# LEDs.net
KiCad netlist of a schematic drawn in Altium Designer
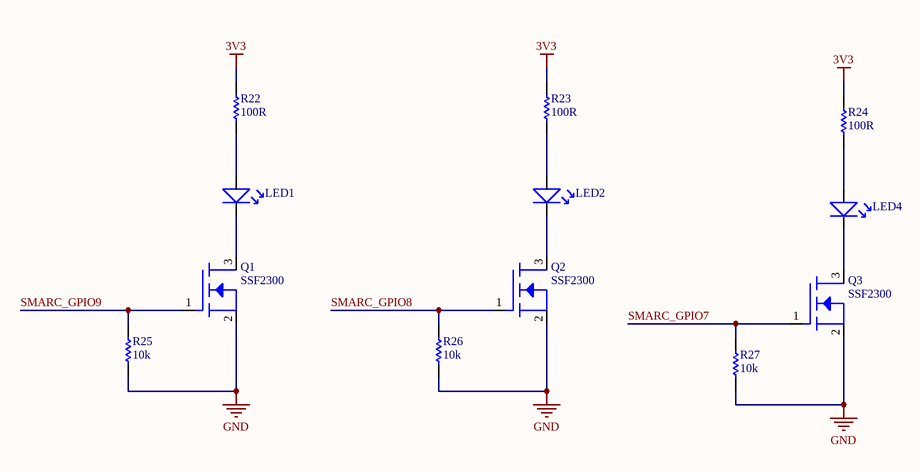
[diagram p0: LEDs.SchDoc]

(export (version "E")
  (design (tool "Eeschema 10.0.6"))
  (components
    (comp (ref "LED1") (value "0603 LED") (footprint "0603 LED") (libsource (lib "Master") (part "0603 LED")))
    (comp (ref "LED2") (value "0603 LED") (footprint "0603 LED") (libsource (lib "Master") (part "0603 LED")))
    (comp (ref "LED4") (value "0603 LED") (footprint "0603 LED") (libsource (lib "Master") (part "0603 LED")))
    (comp (ref "Q1")
      (value "SSF2300")
      (footprint "SSF2300")
      (description "NMOS 20V 4.5A SOT23")
      (libsource (lib "Master") (part "SSF2300"))
    )
    (comp (ref "Q2")
      (value "SSF2300")
      (footprint "SSF2300")
      (description "NMOS 20V 4.5A SOT23")
      (libsource (lib "Master") (part "SSF2300"))
    )
    (comp (ref "Q3")
      (value "SSF2300")
      (footprint "SSF2300")
      (description "NMOS 20V 4.5A SOT23")
      (libsource (lib "Master") (part "SSF2300"))
    )
    (comp (ref "R22")
      (value "100R")
      (footprint "RES-0603")
      (description "Resistor chip. 0603")
      (libsource (lib "Master") (part "RES-0603"))
    )
    (comp (ref "R23")
      (value "100R")
      (footprint "RES-0603")
      (description "Resistor chip. 0603")
      (libsource (lib "Master") (part "RES-0603"))
    )
    (comp (ref "R24")
      (value "100R")
      (footprint "RES-0603")
      (description "Resistor chip. 0603")
      (libsource (lib "Master") (part "RES-0603"))
    )
    (comp (ref "R25")
      (value "10k")
      (footprint "RES-0603")
      (description "Resistor chip. 0603")
      (libsource (lib "Master") (part "RES-0603"))
    )
    (comp (ref "R26")
      (value "10k")
      (footprint "RES-0603")
      (description "Resistor chip. 0603")
      (libsource (lib "Master") (part "RES-0603"))
    )
    (comp (ref "R27")
      (value "10k")
      (footprint "RES-0603")
      (description "Resistor chip. 0603")
      (libsource (lib "Master") (part "RES-0603"))
    )
  )
  (nets
    (net (code "1") (name "/SMARC_GPIO7") (class "Default")
      (node (ref "Q3") (pin "1") (pintype "passive"))
      (node (ref "R27") (pin "2") (pintype "passive"))
    )
    (net (code "2") (name "/SMARC_GPIO8") (class "Default")
      (node (ref "Q2") (pin "1") (pintype "passive"))
      (node (ref "R26") (pin "2") (pintype "passive"))
    )
    (net (code "3") (name "/SMARC_GPIO9") (class "Default")
      (node (ref "Q1") (pin "1") (pintype "passive"))
      (node (ref "R25") (pin "2") (pintype "passive"))
    )
    (net (code "4") (name "3V3") (class "Default")
      (node (ref "R22") (pin "2") (pintype "passive"))
      (node (ref "R23") (pin "2") (pintype "passive"))
      (node (ref "R24") (pin "2") (pintype "passive"))
    )
    (net (code "5") (name "GND") (class "Default")
      (node (ref "Q1") (pin "2") (pintype "passive"))
      (node (ref "Q2") (pin "2") (pintype "passive"))
      (node (ref "Q3") (pin "2") (pintype "passive"))
      (node (ref "R25") (pin "1") (pintype "passive"))
      (node (ref "R26") (pin "1") (pintype "passive"))
      (node (ref "R27") (pin "1") (pintype "passive"))
    )
    (net (code "6") (name "Net-(LED1-5)") (class "Default")
      (node (ref "LED1") (pin "2") (pinfunction "5_2") (pintype "passive"))
      (node (ref "Q1") (pin "3") (pintype "passive"))
    )
    (net (code "7") (name "Net-(LED1-6)") (class "Default")
      (node (ref "LED1") (pin "1") (pinfunction "6_1") (pintype "passive"))
      (node (ref "R22") (pin "1") (pintype "passive"))
    )
    (net (code "8") (name "Net-(LED2-5)") (class "Default")
      (node (ref "LED2") (pin "2") (pinfunction "5_2") (pintype "passive"))
      (node (ref "Q2") (pin "3") (pintype "passive"))
    )
    (net (code "9") (name "Net-(LED2-6)") (class "Default")
      (node (ref "LED2") (pin "1") (pinfunction "6_1") (pintype "passive"))
      (node (ref "R23") (pin "1") (pintype "passive"))
    )
    (net (code "10") (name "Net-(LED4-5)") (class "Default")
      (node (ref "LED4") (pin "2") (pinfunction "5_2") (pintype "passive"))
      (node (ref "Q3") (pin "3") (pintype "passive"))
    )
    (net (code "11") (name "Net-(LED4-6)") (class "Default")
      (node (ref "LED4") (pin "1") (pinfunction "6_1") (pintype "passive"))
      (node (ref "R24") (pin "1") (pintype "passive"))
    )
  )
)
